# APM_OSD.net
KiCad netlist of a schematic drawn in Altium Designer
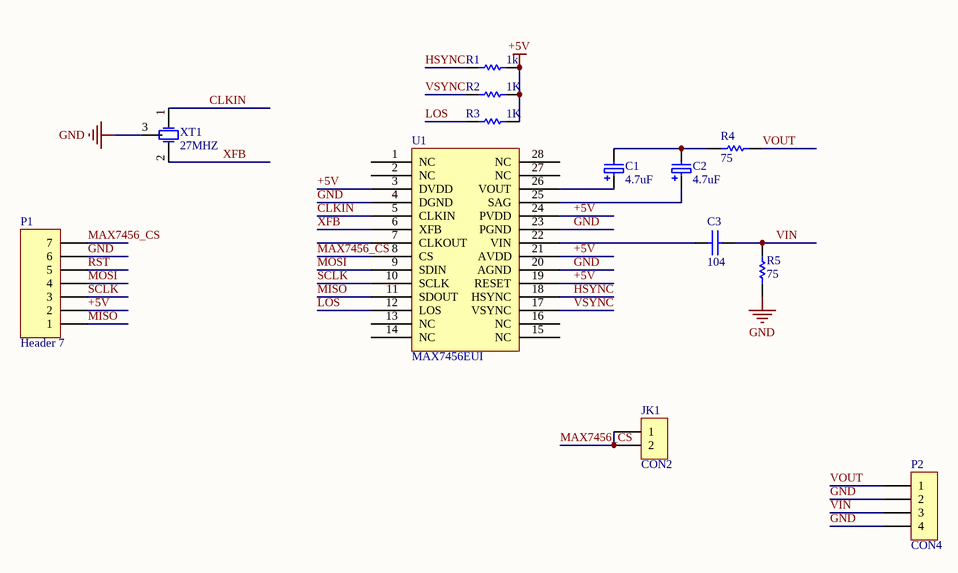
[diagram p0: APM_OSD+.SchDoc]

(export (version "E")
  (design (tool "Eeschema 10.0.6"))
  (components
    (comp (ref "C1")
      (value "4.7uF")
      (footprint "0805C")
      (description "Electrolytic Capacitor 1")
      (libsource (lib "QT_SCH_V2") (part "ELECTRO1"))
    )
    (comp (ref "C2")
      (value "4.7uF")
      (footprint "0805C")
      (description "Electrolytic Capacitor 1")
      (libsource (lib "QT_SCH_V2") (part "ELECTRO1"))
    )
    (comp (ref "C3")
      (value "104")
      (footprint "0402-CAP")
      (description "Capacitor")
      (libsource (lib "*") (part "CAP"))
    )
    (comp (ref "JK1")
      (value "CON2")
      (footprint "1X02-2.0")
      (description "Connector")
      (libsource (lib "接口类") (part "CON2"))
    )
    (comp (ref "P1")
      (value "Header 7")
      (footprint "OSD_7P")
      (description "Header, 7-Pin")
      (libsource (lib "Miscellaneous Connectors") (part "Header 7"))
    )
    (comp (ref "P2")
      (value "CON4")
      (footprint "DF13-4P-1.25DSA")
      (description "Connector")
      (libsource (lib "接口类") (part "CON4"))
    )
    (comp (ref "R1")
      (value "1k")
      (footprint "0402-RES")
      (description "Resistor")
      (libsource (lib "Miscellaneous Devices") (part "Res1"))
    )
    (comp (ref "R2")
      (value "1K")
      (footprint "0402-RES")
      (description "Resistor")
      (libsource (lib "Miscellaneous Devices") (part "Res1"))
    )
    (comp (ref "R3")
      (value "1K")
      (footprint "0402-RES")
      (description "Resistor")
      (libsource (lib "Miscellaneous Devices") (part "Res1"))
    )
    (comp (ref "R4")
      (value "75")
      (footprint "0402-RES")
      (description "Resistor")
      (libsource (lib "Miscellaneous Devices") (part "Res1"))
    )
    (comp (ref "R5")
      (value "75")
      (footprint "0402-RES")
      (description "Resistor")
      (libsource (lib "Miscellaneous Devices") (part "Res1"))
    )
    (comp (ref "U1") (value "MAX7456EUI") (footprint "SSOP-28") (libsource (lib "Schlib1") (part "MAX7456")))
    (comp (ref "XT1") (value "27MHZ") (footprint "27MHZ") (libsource (lib "晶振滤波器") (part "晶振3脚")))
  )
  (nets
    (net (code "1") (name "+5V") (class "Default")
      (node (ref "P1") (pin "2") (pinfunction "2_2") (pintype "passive"))
      (node (ref "R1") (pin "1") (pinfunction "1_1") (pintype "passive"))
      (node (ref "R2") (pin "2") (pinfunction "2_2") (pintype "passive"))
      (node (ref "R3") (pin "2") (pinfunction "2_2") (pintype "passive"))
      (node (ref "U1") (pin "19") (pinfunction "RESET_19") (pintype "passive"))
      (node (ref "U1") (pin "21") (pinfunction "AVDD_21") (pintype "passive"))
      (node (ref "U1") (pin "24") (pinfunction "PVDD_24") (pintype "passive"))
      (node (ref "U1") (pin "3") (pinfunction "DVDD_3") (pintype "passive"))
    )
    (net (code "2") (name "/CLKIN") (class "Default")
      (node (ref "U1") (pin "5") (pinfunction "CLKIN_5") (pintype "passive"))
      (node (ref "XT1") (pin "1") (pinfunction "1_1") (pintype "passive"))
    )
    (net (code "3") (name "/HSYNC") (class "Default")
      (node (ref "R1") (pin "2") (pinfunction "2_2") (pintype "passive"))
      (node (ref "U1") (pin "18") (pinfunction "HSYNC_18") (pintype "passive"))
    )
    (net (code "4") (name "/LOS") (class "Default")
      (node (ref "R3") (pin "1") (pinfunction "1_1") (pintype "passive"))
      (node (ref "U1") (pin "12") (pinfunction "LOS_12") (pintype "passive"))
    )
    (net (code "5") (name "/MAX7456_CS") (class "Default")
      (node (ref "JK1") (pin "1") (pinfunction "1_1") (pintype "passive"))
      (node (ref "JK1") (pin "2") (pinfunction "2_2") (pintype "passive"))
      (node (ref "P1") (pin "7") (pinfunction "7_7") (pintype "passive"))
      (node (ref "U1") (pin "8") (pinfunction "CS_8") (pintype "passive"))
    )
    (net (code "6") (name "/MISO") (class "Default")
      (node (ref "P1") (pin "1") (pinfunction "1_1") (pintype "passive"))
      (node (ref "U1") (pin "11") (pinfunction "SDOUT_11") (pintype "passive"))
    )
    (net (code "7") (name "/MOSI") (class "Default")
      (node (ref "P1") (pin "4") (pinfunction "4_4") (pintype "passive"))
      (node (ref "U1") (pin "9") (pinfunction "SDIN_9") (pintype "passive"))
    )
    (net (code "8") (name "/RST") (class "Default")
      (node (ref "P1") (pin "5") (pinfunction "5_5") (pintype "passive"))
    )
    (net (code "9") (name "/SCLK") (class "Default")
      (node (ref "P1") (pin "3") (pinfunction "3_3") (pintype "passive"))
      (node (ref "U1") (pin "10") (pinfunction "SCLK_10") (pintype "passive"))
    )
    (net (code "10") (name "/VIN") (class "Default")
      (node (ref "C3") (pin "2") (pinfunction "2_2") (pintype "passive"))
      (node (ref "P2") (pin "3") (pinfunction "3_3") (pintype "passive"))
      (node (ref "R5") (pin "2") (pinfunction "2_2") (pintype "passive"))
    )
    (net (code "11") (name "/VOUT") (class "Default")
      (node (ref "P2") (pin "1") (pinfunction "1_1") (pintype "passive"))
      (node (ref "R4") (pin "2") (pinfunction "2_2") (pintype "passive"))
    )
    (net (code "12") (name "/VSYNC") (class "Default")
      (node (ref "R2") (pin "1") (pinfunction "1_1") (pintype "passive"))
      (node (ref "U1") (pin "17") (pinfunction "VSYNC_17") (pintype "passive"))
    )
    (net (code "13") (name "/XFB") (class "Default")
      (node (ref "U1") (pin "6") (pinfunction "XFB_6") (pintype "passive"))
      (node (ref "XT1") (pin "2") (pinfunction "2_2") (pintype "passive"))
    )
    (net (code "14") (name "GND") (class "Default")
      (node (ref "P1") (pin "6") (pinfunction "6_6") (pintype "passive"))
      (node (ref "P2") (pin "2") (pinfunction "2_2") (pintype "passive"))
      (node (ref "P2") (pin "4") (pinfunction "4_4") (pintype "passive"))
      (node (ref "R5") (pin "1") (pinfunction "1_1") (pintype "passive"))
      (node (ref "U1") (pin "20") (pinfunction "AGND_20") (pintype "passive"))
      (node (ref "U1") (pin "23") (pinfunction "PGND_23") (pintype "passive"))
      (node (ref "U1") (pin "4") (pinfunction "DGND_4") (pintype "passive"))
      (node (ref "XT1") (pin "3") (pinfunction "3_3") (pintype "passive"))
    )
    (net (code "15") (name "Net-(C1-Pad2)") (class "Default")
      (node (ref "C1") (pin "2") (pinfunction "2_2") (pintype "passive"))
      (node (ref "C2") (pin "2") (pinfunction "2_2") (pintype "passive"))
      (node (ref "R4") (pin "1") (pinfunction "1_1") (pintype "passive"))
    )
    (net (code "16") (name "Net-(U1-SAG)") (class "Default")
      (node (ref "C2") (pin "1") (pinfunction "1_1") (pintype "passive"))
      (node (ref "U1") (pin "25") (pinfunction "SAG_25") (pintype "passive"))
    )
    (net (code "17") (name "Net-(U1-VIN)") (class "Default")
      (node (ref "C3") (pin "1") (pinfunction "1_1") (pintype "passive"))
      (node (ref "U1") (pin "22") (pinfunction "VIN_22") (pintype "passive"))
    )
    (net (code "18") (name "Net-(U1-VOUT)") (class "Default")
      (node (ref "C1") (pin "1") (pinfunction "1_1") (pintype "passive"))
      (node (ref "U1") (pin "26") (pinfunction "VOUT_26") (pintype "passive"))
    )
    (net (code "19") (name "unconnected-(U1-CLKOUT-Pad7)") (class "Default")
      (node (ref "U1") (pin "7") (pinfunction "CLKOUT_7") (pintype "passive"))
    )
    (net (code "20") (name "unconnected-(U1-NC-Pad1)") (class "Default")
      (node (ref "U1") (pin "1") (pinfunction "NC_1") (pintype "passive"))
    )
    (net (code "21") (name "unconnected-(U1-NC-Pad2)") (class "Default")
      (node (ref "U1") (pin "2") (pinfunction "NC_2") (pintype "passive"))
    )
    (net (code "22") (name "unconnected-(U1-NC-Pad13)") (class "Default")
      (node (ref "U1") (pin "13") (pinfunction "NC_13") (pintype "passive"))
    )
    (net (code "23") (name "unconnected-(U1-NC-Pad14)") (class "Default")
      (node (ref "U1") (pin "14") (pinfunction "NC_14") (pintype "passive"))
    )
    (net (code "24") (name "unconnected-(U1-NC-Pad15)") (class "Default")
      (node (ref "U1") (pin "15") (pinfunction "NC_15") (pintype "passive"))
    )
    (net (code "25") (name "unconnected-(U1-NC-Pad16)") (class "Default")
      (node (ref "U1") (pin "16") (pinfunction "NC_16") (pintype "passive"))
    )
    (net (code "26") (name "unconnected-(U1-NC-Pad27)") (class "Default")
      (node (ref "U1") (pin "27") (pinfunction "NC_27") (pintype "passive"))
    )
    (net (code "27") (name "unconnected-(U1-NC-Pad28)") (class "Default")
      (node (ref "U1") (pin "28") (pinfunction "NC_28") (pintype "passive"))
    )
  )
)
